# controller-ha-v5.net
KiCad netlist of a schematic drawn in EAGLE
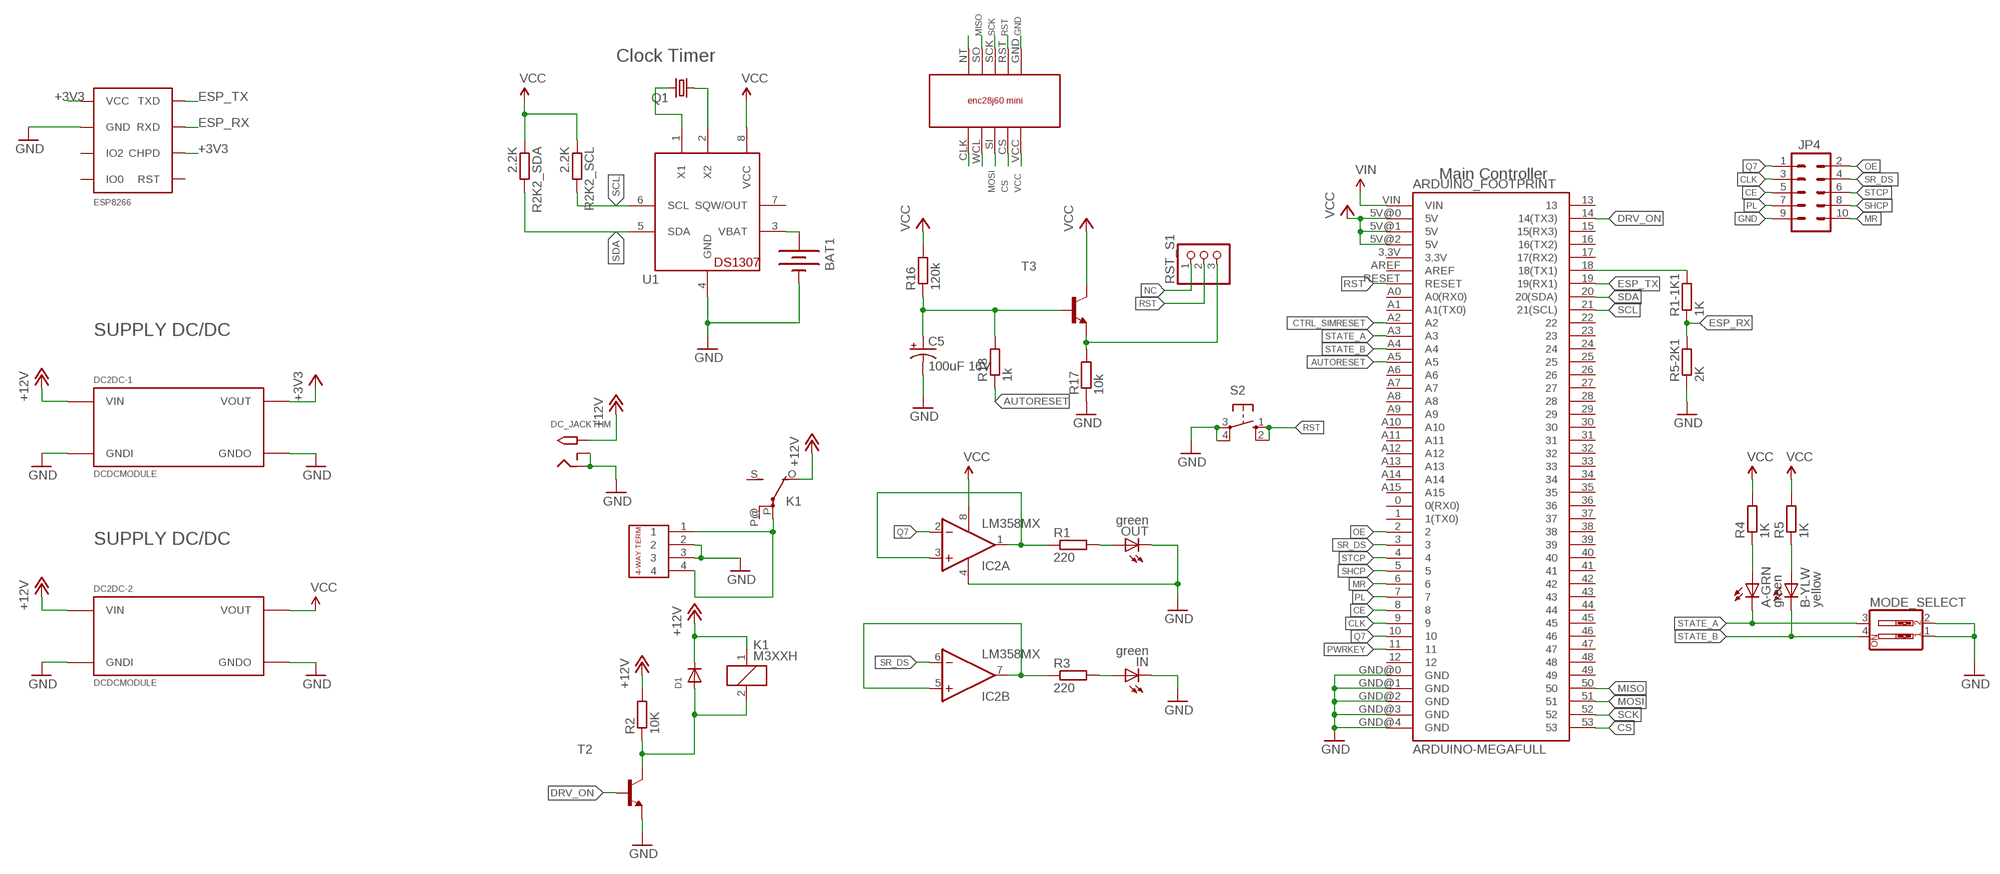
[diagram p0: schematic, sheet 1]

(export (version "E")
  (design (tool "Eeschema 10.0.6"))
  (components
    (comp (ref "4-WAY_L-TERMINAL")
      (value "4-PIN-CON-1759017")
      (footprint "eagle-import:4-PIN-CON-1759017")
      (libsource (lib "eagle-import") (part "4-PIN-CON-1759017"))
    )
    (comp (ref "A-GRN")
      (value "green")
      (footprint "eagle-import:CHIP-LED0805")
      (libsource (lib "eagle-import") (part "led_LEDCHIP-LED0805"))
    )
    (comp (ref "ARDUINO_FOOTPRINT")
      (value "ARDUINO-MEGAFULL")
      (footprint "eagle-import:ARDUINO_MEGA")
      (libsource (lib "eagle-import") (part "ARDUINO-MEGAFULL"))
    )
    (comp (ref "B-YLW")
      (value "yellow")
      (footprint "eagle-import:CHIP-LED0805")
      (libsource (lib "eagle-import") (part "led_LEDCHIP-LED0805"))
    )
    (comp (ref "BAT1")
      (value "BATTERY20PTH")
      (footprint "eagle-import:BATTCOM_20MM_PTH")
      (libsource (lib "eagle-import") (part "BATTERY20PTH"))
    )
    (comp (ref "C5")
      (value "100uF 16V")
      (footprint "eagle-import:153CLV-0605")
      (libsource (lib "eagle-import") (part "CPOL-US153CLV-0605"))
    )
    (comp (ref "D1")
      (value "DIODESMA")
      (footprint "eagle-import:SMADIODE")
      (libsource (lib "eagle-import") (part "DIODESMA"))
    )
    (comp (ref "DC2DC-1")
      (value "DCDCMODULE")
      (footprint "eagle-import:DCDCMODULE")
      (libsource (lib "eagle-import") (part "DCDCMODULE"))
    )
    (comp (ref "DC2DC-2")
      (value "DCDCMODULE")
      (footprint "eagle-import:DCDCMODULE")
      (libsource (lib "eagle-import") (part "DCDCMODULE"))
    )
    (comp (ref "DC_JACKTHM")
      (value "2.1MMJACKTHM")
      (footprint "eagle-import:PJ-102A")
      (libsource (lib "eagle-import") (part "2.1MMJACKTHM"))
    )
    (comp (ref "ESP8266")
      (value "ESP8266")
      (footprint "eagle-import:ESP8266")
      (libsource (lib "eagle-import") (part "ESP8266"))
    )
    (comp (ref "IC2")
      (value "LM358MX")
      (footprint "eagle-import:SO08")
      (libsource (lib "eagle-import") (part "LM358MX"))
    )
    (comp (ref "IN")
      (value "green")
      (footprint "eagle-import:CHIPLED_0805")
      (libsource (lib "eagle-import") (part "LEDCHIPLED_0805"))
    )
    (comp (ref "JP4")
      (value "M05X2RA")
      (footprint "eagle-import:2X5-RA")
      (libsource (lib "eagle-import") (part "M05X2RA"))
    )
    (comp (ref "K1")
      (value "M3XXH")
      (footprint "eagle-import:M3XXH")
      (libsource (lib "eagle-import") (part "M3XXH"))
    )
    (comp (ref "MODE_SELECT")
      (value "SW_DIP-2")
      (footprint "eagle-import:EDG-02")
      (libsource (lib "eagle-import") (part "SW_DIP-2"))
    )
    (comp (ref "OUT")
      (value "green")
      (footprint "eagle-import:CHIPLED_0805")
      (libsource (lib "eagle-import") (part "LEDCHIPLED_0805"))
    )
    (comp (ref "Q1")
      (value "CRYSTALTC26H")
      (footprint "eagle-import:TC26H")
      (libsource (lib "eagle-import") (part "CRYSTALTC26H"))
    )
    (comp (ref "R1")
      (value "220")
      (footprint "eagle-import:R0805")
      (libsource (lib "eagle-import") (part "resistor_R-EU_R0805"))
    )
    (comp (ref "R1-1K1")
      (value "1K")
      (footprint "eagle-import:R0603")
      (libsource (lib "eagle-import") (part "R-EU_R0603"))
    )
    (comp (ref "R2")
      (value "10K")
      (footprint "eagle-import:R0805")
      (libsource (lib "eagle-import") (part "resistor_R-EU_R0805"))
    )
    (comp (ref "R2K2_SCL")
      (value "2.2K")
      (footprint "eagle-import:R0603")
      (libsource (lib "eagle-import") (part "R-EU_R0603"))
    )
    (comp (ref "R2K2_SDA")
      (value "2.2K")
      (footprint "eagle-import:R0603")
      (libsource (lib "eagle-import") (part "R-EU_R0603"))
    )
    (comp (ref "R3")
      (value "220")
      (footprint "eagle-import:R0805")
      (libsource (lib "eagle-import") (part "resistor_R-EU_R0805"))
    )
    (comp (ref "R4")
      (value "1K")
      (footprint "eagle-import:R0805")
      (libsource (lib "eagle-import") (part "resistor_R-EU_R0805"))
    )
    (comp (ref "R5")
      (value "1K")
      (footprint "eagle-import:R0805")
      (libsource (lib "eagle-import") (part "resistor_R-EU_R0805"))
    )
    (comp (ref "R5-2K1")
      (value "2K")
      (footprint "eagle-import:R0603")
      (libsource (lib "eagle-import") (part "R-EU_R0603"))
    )
    (comp (ref "R16")
      (value "120k")
      (footprint "eagle-import:R0805")
      (libsource (lib "eagle-import") (part "R-EU_R0805"))
    )
    (comp (ref "R17")
      (value "10k")
      (footprint "eagle-import:R0805")
      (libsource (lib "eagle-import") (part "R-EU_R0805"))
    )
    (comp (ref "R18")
      (value "1k")
      (footprint "eagle-import:R0805")
      (libsource (lib "eagle-import") (part "R-EU_R0805"))
    )
    (comp (ref "RST_S1")
      (value "PINHD-1X3CB")
      (footprint "eagle-import:1X03-CLEANBIG")
      (libsource (lib "eagle-import") (part "PINHD-1X3CB"))
    )
    (comp (ref "S2")
      (value "10-XX")
      (footprint "eagle-import:B3F-10XX")
      (fields (field (name "MPN") "B3F-1000"))
      (libsource (lib "eagle-import") (part "10-XX"))
    )
    (comp (ref "T2")
      (value "MMBT2222ALT1-NPN-SOT23-BEC")
      (footprint "eagle-import:SOT23-BEC")
      (libsource (lib "eagle-import") (part "-NPN-SOT23-BECMMBT2222ALT1"))
    )
    (comp (ref "T3")
      (value "MMBT2222ALT1-NPN-SOT23-BEC")
      (footprint "eagle-import:SOT23-BEC")
      (libsource (lib "eagle-import") (part "-NPN-SOT23-BECMMBT2222ALT1"))
    )
    (comp (ref "U$2")
      (value "ENC28J60_MODULE_BOTTOM")
      (footprint "eagle-import:ENC28J60_MODULE_BOTTOM")
      (libsource (lib "eagle-import") (part "ENC28J60_MODULE_BOTTOM"))
    )
    (comp (ref "U1")
      (value "DS1307")
      (footprint "eagle-import:DIL08")
      (libsource (lib "eagle-import") (part "DS1307"))
    )
  )
  (nets
    (net (code "1") (name "+3V3") (class "Default")
      (node (ref "DC2DC-1") (pin "VOUT") (pinfunction "VOUT_VOUT") (pintype "bidirectional"))
      (node (ref "ESP8266") (pin "CHPD") (pinfunction "CHPD_CHPD") (pintype "bidirectional"))
      (node (ref "ESP8266") (pin "VCC") (pinfunction "VCC_VCC") (pintype "bidirectional"))
    )
    (net (code "2") (name "+12V") (class "Default")
      (node (ref "D1") (pin "C") (pinfunction "C_C") (pintype "passive"))
      (node (ref "DC2DC-1") (pin "VIN") (pinfunction "VIN_VIN") (pintype "bidirectional"))
      (node (ref "DC2DC-2") (pin "VIN") (pinfunction "VIN_VIN") (pintype "bidirectional"))
      (node (ref "DC_JACKTHM") (pin "TIP") (pinfunction "TIP_TIP") (pintype "bidirectional"))
      (node (ref "K1") (pin "1") (pinfunction "1_1") (pintype "passive"))
      (node (ref "K1") (pin "O") (pinfunction "O_O") (pintype "passive"))
      (node (ref "R2") (pin "2") (pinfunction "2_2") (pintype "passive"))
    )
    (net (code "3") (name "AUTORESET") (class "Default")
      (node (ref "ARDUINO_FOOTPRINT") (pin "A5") (pinfunction "A5_A5") (pintype "bidirectional"))
      (node (ref "R18") (pin "1") (pinfunction "1_1") (pintype "passive"))
    )
    (net (code "4") (name "CE") (class "Default")
      (node (ref "ARDUINO_FOOTPRINT") (pin "8") (pinfunction "8_8") (pintype "bidirectional"))
      (node (ref "JP4") (pin "5") (pinfunction "5_5") (pintype "passive"))
    )
    (net (code "5") (name "CLK") (class "Default")
      (node (ref "ARDUINO_FOOTPRINT") (pin "9") (pinfunction "9_9") (pintype "bidirectional"))
      (node (ref "JP4") (pin "3") (pinfunction "3_3") (pintype "passive"))
    )
    (net (code "6") (name "CS") (class "Default")
      (node (ref "ARDUINO_FOOTPRINT") (pin "53") (pinfunction "53_53") (pintype "bidirectional"))
      (node (ref "U$2") (pin "CS") (pinfunction "CS_CS") (pintype "bidirectional"))
    )
    (net (code "7") (name "CTRL_SIMRESET") (class "Default")
      (node (ref "ARDUINO_FOOTPRINT") (pin "A2") (pinfunction "A2_A2") (pintype "bidirectional"))
    )
    (net (code "8") (name "DRV_ON") (class "Default")
      (node (ref "ARDUINO_FOOTPRINT") (pin "14") (pinfunction "14(TX3)_14") (pintype "bidirectional"))
      (node (ref "T2") (pin "B") (pinfunction "B_B") (pintype "passive"))
    )
    (net (code "9") (name "ESP_RX") (class "Default")
      (node (ref "ESP8266") (pin "RXD") (pinfunction "RXD_RXD") (pintype "bidirectional"))
      (node (ref "R1-1K1") (pin "1") (pinfunction "1_1") (pintype "passive"))
      (node (ref "R5-2K1") (pin "2") (pinfunction "2_2") (pintype "passive"))
    )
    (net (code "10") (name "ESP_TX") (class "Default")
      (node (ref "ARDUINO_FOOTPRINT") (pin "19") (pinfunction "19(RX1)_19") (pintype "bidirectional"))
      (node (ref "ESP8266") (pin "TXD") (pinfunction "TXD_TXD") (pintype "bidirectional"))
    )
    (net (code "11") (name "GND") (class "Default")
      (node (ref "4-WAY_L-TERMINAL") (pin "2") (pinfunction "2_2") (pintype "bidirectional"))
      (node (ref "4-WAY_L-TERMINAL") (pin "3") (pinfunction "3_3") (pintype "bidirectional"))
      (node (ref "ARDUINO_FOOTPRINT") (pin "GND@0") (pinfunction "GND_GND@0") (pintype "bidirectional"))
      (node (ref "ARDUINO_FOOTPRINT") (pin "GND@1") (pinfunction "GND_GND@1") (pintype "bidirectional"))
      (node (ref "ARDUINO_FOOTPRINT") (pin "GND@2") (pinfunction "GND_GND@2") (pintype "bidirectional"))
      (node (ref "ARDUINO_FOOTPRINT") (pin "GND@3") (pinfunction "GND_GND@3") (pintype "bidirectional"))
      (node (ref "ARDUINO_FOOTPRINT") (pin "GND@4") (pinfunction "GND_GND@4") (pintype "bidirectional"))
      (node (ref "BAT1") (pin "2") (pinfunction "-_2") (pintype "power_in"))
      (node (ref "C5") (pin "-") (pinfunction "-_-") (pintype "passive"))
      (node (ref "DC2DC-1") (pin "GND#0") (pinfunction "GNDI_GND#0") (pintype "bidirectional"))
      (node (ref "DC2DC-1") (pin "GND#1") (pinfunction "GNDO_GND#1") (pintype "bidirectional"))
      (node (ref "DC2DC-2") (pin "GND#0") (pinfunction "GNDI_GND#0") (pintype "bidirectional"))
      (node (ref "DC2DC-2") (pin "GND#1") (pinfunction "GNDO_GND#1") (pintype "bidirectional"))
      (node (ref "DC_JACKTHM") (pin "RING") (pinfunction "RING_RING") (pintype "bidirectional"))
      (node (ref "DC_JACKTHM") (pin "RING_SW") (pinfunction "RING_SW_RING_SW") (pintype "bidirectional"))
      (node (ref "ESP8266") (pin "GND") (pinfunction "GND_GND") (pintype "bidirectional"))
      (node (ref "IC2") (pin "4") (pinfunction "V-_4") (pintype "power_in"))
      (node (ref "IN") (pin "C") (pinfunction "C_C") (pintype "passive"))
      (node (ref "JP4") (pin "9") (pinfunction "9_9") (pintype "passive"))
      (node (ref "MODE_SELECT") (pin "1") (pinfunction "1_1") (pintype "passive"))
      (node (ref "MODE_SELECT") (pin "2") (pinfunction "2_2") (pintype "passive"))
      (node (ref "OUT") (pin "C") (pinfunction "C_C") (pintype "passive"))
      (node (ref "R17") (pin "1") (pinfunction "1_1") (pintype "passive"))
      (node (ref "R5-2K1") (pin "1") (pinfunction "1_1") (pintype "passive"))
      (node (ref "S2") (pin "3") (pinfunction "P_3") (pintype "passive"))
      (node (ref "S2") (pin "4") (pinfunction "P1_4") (pintype "passive"))
      (node (ref "T2") (pin "E") (pinfunction "E_E") (pintype "passive"))
      (node (ref "U$2") (pin "GND") (pinfunction "GND_GND") (pintype "bidirectional"))
      (node (ref "U1") (pin "4") (pinfunction "GND_4") (pintype "power_in"))
    )
    (net (code "12") (name "MISO") (class "Default")
      (node (ref "ARDUINO_FOOTPRINT") (pin "50") (pinfunction "50_50") (pintype "bidirectional"))
      (node (ref "U$2") (pin "SO") (pinfunction "SO_SO") (pintype "bidirectional"))
    )
    (net (code "13") (name "MOSI") (class "Default")
      (node (ref "ARDUINO_FOOTPRINT") (pin "51") (pinfunction "51_51") (pintype "bidirectional"))
      (node (ref "U$2") (pin "SI") (pinfunction "SI_SI") (pintype "bidirectional"))
    )
    (net (code "14") (name "MR") (class "Default")
      (node (ref "ARDUINO_FOOTPRINT") (pin "6") (pinfunction "6_6") (pintype "bidirectional"))
      (node (ref "JP4") (pin "10") (pinfunction "10_10") (pintype "passive"))
    )
    (net (code "15") (name "NC") (class "Default")
      (node (ref "RST_S1") (pin "1") (pinfunction "1_1") (pintype "passive"))
    )
    (net (code "16") (name "Net-(4-WAY_L-TERMINAL-Pad1)") (class "Default")
      (node (ref "4-WAY_L-TERMINAL") (pin "1") (pinfunction "1_1") (pintype "bidirectional"))
      (node (ref "4-WAY_L-TERMINAL") (pin "4") (pinfunction "4_4") (pintype "bidirectional"))
      (node (ref "K1") (pin "P") (pinfunction "P_P") (pintype "passive"))
    )
    (net (code "17") (name "Net-(A-GRN-PadA)") (class "Default")
      (node (ref "A-GRN") (pin "A") (pinfunction "A_A") (pintype "passive"))
      (node (ref "R4") (pin "1") (pinfunction "1_1") (pintype "passive"))
    )
    (net (code "18") (name "Net-(ARDUINO_FOOTPRINT-18(TX1))") (class "Default")
      (node (ref "ARDUINO_FOOTPRINT") (pin "18") (pinfunction "18(TX1)_18") (pintype "bidirectional"))
      (node (ref "R1-1K1") (pin "2") (pinfunction "2_2") (pintype "passive"))
    )
    (net (code "19") (name "Net-(B-YLW-PadA)") (class "Default")
      (node (ref "B-YLW") (pin "A") (pinfunction "A_A") (pintype "passive"))
      (node (ref "R5") (pin "1") (pinfunction "1_1") (pintype "passive"))
    )
    (net (code "20") (name "Net-(BAT1-+)") (class "Default")
      (node (ref "BAT1") (pin "1") (pinfunction "+_1") (pintype "power_in"))
      (node (ref "U1") (pin "3") (pinfunction "VBAT_3") (pintype "power_in"))
    )
    (net (code "21") (name "Net-(C5-Pad+)") (class "Default")
      (node (ref "C5") (pin "+") (pinfunction "+_+") (pintype "passive"))
      (node (ref "R16") (pin "1") (pinfunction "1_1") (pintype "passive"))
      (node (ref "R18") (pin "2") (pinfunction "2_2") (pintype "passive"))
      (node (ref "T3") (pin "B") (pinfunction "B_B") (pintype "passive"))
    )
    (net (code "22") (name "Net-(D1-PadA)") (class "Default")
      (node (ref "D1") (pin "A") (pinfunction "A_A") (pintype "passive"))
      (node (ref "K1") (pin "2") (pinfunction "2_2") (pintype "passive"))
      (node (ref "R2") (pin "1") (pinfunction "1_1") (pintype "passive"))
      (node (ref "T2") (pin "C") (pinfunction "C_C") (pintype "passive"))
    )
    (net (code "23") (name "Net-(IC2A-+IN)") (class "Default")
      (node (ref "IC2") (pin "1") (pinfunction "OUT_1") (pintype "output"))
      (node (ref "IC2") (pin "3") (pinfunction "+IN_3") (pintype "input"))
      (node (ref "R1") (pin "1") (pinfunction "1_1") (pintype "passive"))
    )
    (net (code "24") (name "Net-(IC2B-+IN)") (class "Default")
      (node (ref "IC2") (pin "5") (pinfunction "+IN_5") (pintype "input"))
      (node (ref "IC2") (pin "7") (pinfunction "OUT_7") (pintype "output"))
      (node (ref "R3") (pin "1") (pinfunction "1_1") (pintype "passive"))
    )
    (net (code "25") (name "Net-(IN-PadA)") (class "Default")
      (node (ref "IN") (pin "A") (pinfunction "A_A") (pintype "passive"))
      (node (ref "R3") (pin "2") (pinfunction "2_2") (pintype "passive"))
    )
    (net (code "26") (name "Net-(OUT-PadA)") (class "Default")
      (node (ref "OUT") (pin "A") (pinfunction "A_A") (pintype "passive"))
      (node (ref "R1") (pin "2") (pinfunction "2_2") (pintype "passive"))
    )
    (net (code "27") (name "Net-(R17-Pad2)") (class "Default")
      (node (ref "R17") (pin "2") (pinfunction "2_2") (pintype "passive"))
      (node (ref "RST_S1") (pin "3") (pinfunction "3_3") (pintype "passive"))
      (node (ref "T3") (pin "E") (pinfunction "E_E") (pintype "passive"))
    )
    (net (code "28") (name "Net-(U1-X1)") (class "Default")
      (node (ref "Q1") (pin "2") (pinfunction "2_2") (pintype "passive"))
      (node (ref "U1") (pin "1") (pinfunction "X1_1") (pintype "passive"))
    )
    (net (code "29") (name "Net-(U1-X2)") (class "Default")
      (node (ref "Q1") (pin "1") (pinfunction "1_1") (pintype "passive"))
      (node (ref "U1") (pin "2") (pinfunction "X2_2") (pintype "passive"))
    )
    (net (code "30") (name "OE") (class "Default")
      (node (ref "ARDUINO_FOOTPRINT") (pin "2") (pinfunction "2_2") (pintype "bidirectional"))
      (node (ref "JP4") (pin "2") (pinfunction "2_2") (pintype "passive"))
    )
    (net (code "31") (name "PL") (class "Default")
      (node (ref "ARDUINO_FOOTPRINT") (pin "7") (pinfunction "7_7") (pintype "bidirectional"))
      (node (ref "JP4") (pin "7") (pinfunction "7_7") (pintype "passive"))
    )
    (net (code "32") (name "PWRKEY") (class "Default")
      (node (ref "ARDUINO_FOOTPRINT") (pin "11") (pinfunction "11_11") (pintype "bidirectional"))
    )
    (net (code "33") (name "Q7") (class "Default")
      (node (ref "ARDUINO_FOOTPRINT") (pin "10") (pinfunction "10_10") (pintype "bidirectional"))
      (node (ref "IC2") (pin "2") (pinfunction "-IN_2") (pintype "input"))
      (node (ref "JP4") (pin "1") (pinfunction "1_1") (pintype "passive"))
    )
    (net (code "34") (name "RST") (class "Default")
      (node (ref "ARDUINO_FOOTPRINT") (pin "RESET") (pinfunction "RESET_RESET") (pintype "bidirectional"))
      (node (ref "RST_S1") (pin "2") (pinfunction "2_2") (pintype "passive"))
      (node (ref "S2") (pin "1") (pinfunction "S_1") (pintype "passive"))
      (node (ref "S2") (pin "2") (pinfunction "S1_2") (pintype "passive"))
      (node (ref "U$2") (pin "RST") (pinfunction "RST_RST") (pintype "bidirectional"))
    )
    (net (code "35") (name "SCK") (class "Default")
      (node (ref "ARDUINO_FOOTPRINT") (pin "52") (pinfunction "52_52") (pintype "bidirectional"))
      (node (ref "U$2") (pin "SCK") (pinfunction "SCK_SCK") (pintype "bidirectional"))
    )
    (net (code "36") (name "SCL") (class "Default")
      (node (ref "ARDUINO_FOOTPRINT") (pin "21") (pinfunction "21(SCL)_21") (pintype "bidirectional"))
      (node (ref "R2K2_SCL") (pin "2") (pinfunction "2_2") (pintype "passive"))
      (node (ref "U1") (pin "6") (pinfunction "SCL_6") (pintype "bidirectional"))
    )
    (net (code "37") (name "SDA") (class "Default")
      (node (ref "ARDUINO_FOOTPRINT") (pin "20") (pinfunction "20(SDA)_20") (pintype "bidirectional"))
      (node (ref "R2K2_SDA") (pin "2") (pinfunction "2_2") (pintype "passive"))
      (node (ref "U1") (pin "5") (pinfunction "SDA_5") (pintype "bidirectional"))
    )
    (net (code "38") (name "SHCP") (class "Default")
      (node (ref "ARDUINO_FOOTPRINT") (pin "5") (pinfunction "5_5") (pintype "bidirectional"))
      (node (ref "JP4") (pin "8") (pinfunction "8_8") (pintype "passive"))
    )
    (net (code "39") (name "SR_DS") (class "Default")
      (node (ref "ARDUINO_FOOTPRINT") (pin "3") (pinfunction "3_3") (pintype "bidirectional"))
      (node (ref "IC2") (pin "6") (pinfunction "-IN_6") (pintype "input"))
      (node (ref "JP4") (pin "4") (pinfunction "4_4") (pintype "passive"))
    )
    (net (code "40") (name "STATE_A") (class "Default")
      (node (ref "A-GRN") (pin "C") (pinfunction "C_C") (pintype "passive"))
      (node (ref "ARDUINO_FOOTPRINT") (pin "A3") (pinfunction "A3_A3") (pintype "bidirectional"))
      (node (ref "MODE_SELECT") (pin "3") (pinfunction "3_3") (pintype "passive"))
    )
    (net (code "41") (name "STATE_B") (class "Default")
      (node (ref "ARDUINO_FOOTPRINT") (pin "A4") (pinfunction "A4_A4") (pintype "bidirectional"))
      (node (ref "B-YLW") (pin "C") (pinfunction "C_C") (pintype "passive"))
      (node (ref "MODE_SELECT") (pin "4") (pinfunction "4_4") (pintype "passive"))
    )
    (net (code "42") (name "STCP") (class "Default")
      (node (ref "ARDUINO_FOOTPRINT") (pin "4") (pinfunction "4_4") (pintype "bidirectional"))
      (node (ref "JP4") (pin "6") (pinfunction "6_6") (pintype "passive"))
    )
    (net (code "43") (name "VCC") (class "Default")
      (node (ref "ARDUINO_FOOTPRINT") (pin "5V@0") (pinfunction "5V_5V@0") (pintype "bidirectional"))
      (node (ref "ARDUINO_FOOTPRINT") (pin "5V@1") (pinfunction "5V_5V@1") (pintype "bidirectional"))
      (node (ref "ARDUINO_FOOTPRINT") (pin "5V@2") (pinfunction "5V_5V@2") (pintype "bidirectional"))
      (node (ref "DC2DC-2") (pin "VOUT") (pinfunction "VOUT_VOUT") (pintype "bidirectional"))
      (node (ref "IC2") (pin "8") (pinfunction "V+_8") (pintype "power_in"))
      (node (ref "R16") (pin "2") (pinfunction "2_2") (pintype "passive"))
      (node (ref "R2K2_SCL") (pin "1") (pinfunction "1_1") (pintype "passive"))
      (node (ref "R2K2_SDA") (pin "1") (pinfunction "1_1") (pintype "passive"))
      (node (ref "R4") (pin "2") (pinfunction "2_2") (pintype "passive"))
      (node (ref "R5") (pin "2") (pinfunction "2_2") (pintype "passive"))
      (node (ref "T3") (pin "C") (pinfunction "C_C") (pintype "passive"))
      (node (ref "U$2") (pin "VCC") (pinfunction "VCC_VCC") (pintype "bidirectional"))
      (node (ref "U1") (pin "8") (pinfunction "VCC_8") (pintype "power_in"))
    )
    (net (code "44") (name "VIN") (class "Default")
      (node (ref "ARDUINO_FOOTPRINT") (pin "VIN") (pinfunction "VIN_VIN") (pintype "bidirectional"))
    )
    (net (code "45") (name "unconnected-(ARDUINO_FOOTPRINT-0(RX0)-Pad0)") (class "Default")
      (node (ref "ARDUINO_FOOTPRINT") (pin "0") (pinfunction "0(RX0)_0") (pintype "bidirectional"))
    )
    (net (code "46") (name "unconnected-(ARDUINO_FOOTPRINT-1(TX0)-Pad1)") (class "Default")
      (node (ref "ARDUINO_FOOTPRINT") (pin "1") (pinfunction "1(TX0)_1") (pintype "bidirectional"))
    )
    (net (code "47") (name "unconnected-(ARDUINO_FOOTPRINT-15(RX3)-Pad15)") (class "Default")
      (node (ref "ARDUINO_FOOTPRINT") (pin "15") (pinfunction "15(RX3)_15") (pintype "bidirectional"))
    )
    (net (code "48") (name "unconnected-(ARDUINO_FOOTPRINT-16(TX2)-Pad16)") (class "Default")
      (node (ref "ARDUINO_FOOTPRINT") (pin "16") (pinfunction "16(TX2)_16") (pintype "bidirectional"))
    )
    (net (code "49") (name "unconnected-(ARDUINO_FOOTPRINT-17(RX2)-Pad17)") (class "Default")
      (node (ref "ARDUINO_FOOTPRINT") (pin "17") (pinfunction "17(RX2)_17") (pintype "bidirectional"))
    )
    (net (code "50") (name "unconnected-(ARDUINO_FOOTPRINT-A0(RX0)-PadA0)") (class "Default")
      (node (ref "ARDUINO_FOOTPRINT") (pin "A0") (pinfunction "A0(RX0)_A0") (pintype "bidirectional"))
    )
    (net (code "51") (name "unconnected-(ARDUINO_FOOTPRINT-A1(TX0)-PadA1)") (class "Default")
      (node (ref "ARDUINO_FOOTPRINT") (pin "A1") (pinfunction "A1(TX0)_A1") (pintype "bidirectional"))
    )
    (net (code "52") (name "unconnected-(ARDUINO_FOOTPRINT-Pad3.3V)") (class "Default")
      (node (ref "ARDUINO_FOOTPRINT") (pin "3.3V") (pinfunction "3.3V_3.3V") (pintype "bidirectional"))
    )
    (net (code "53") (name "unconnected-(ARDUINO_FOOTPRINT-Pad12)") (class "Default")
      (node (ref "ARDUINO_FOOTPRINT") (pin "12") (pinfunction "12_12") (pintype "bidirectional"))
    )
    (net (code "54") (name "unconnected-(ARDUINO_FOOTPRINT-Pad13)") (class "Default")
      (node (ref "ARDUINO_FOOTPRINT") (pin "13") (pinfunction "13_13") (pintype "bidirectional"))
    )
    (net (code "55") (name "unconnected-(ARDUINO_FOOTPRINT-Pad22)") (class "Default")
      (node (ref "ARDUINO_FOOTPRINT") (pin "22") (pinfunction "22_22") (pintype "bidirectional"))
    )
    (net (code "56") (name "unconnected-(ARDUINO_FOOTPRINT-Pad23)") (class "Default")
      (node (ref "ARDUINO_FOOTPRINT") (pin "23") (pinfunction "23_23") (pintype "bidirectional"))
    )
    (net (code "57") (name "unconnected-(ARDUINO_FOOTPRINT-Pad24)") (class "Default")
      (node (ref "ARDUINO_FOOTPRINT") (pin "24") (pinfunction "24_24") (pintype "bidirectional"))
    )
    (net (code "58") (name "unconnected-(ARDUINO_FOOTPRINT-Pad25)") (class "Default")
      (node (ref "ARDUINO_FOOTPRINT") (pin "25") (pinfunction "25_25") (pintype "bidirectional"))
    )
    (net (code "59") (name "unconnected-(ARDUINO_FOOTPRINT-Pad26)") (class "Default")
      (node (ref "ARDUINO_FOOTPRINT") (pin "26") (pinfunction "26_26") (pintype "bidirectional"))
    )
    (net (code "60") (name "unconnected-(ARDUINO_FOOTPRINT-Pad27)") (class "Default")
      (node (ref "ARDUINO_FOOTPRINT") (pin "27") (pinfunction "27_27") (pintype "bidirectional"))
    )
    (net (code "61") (name "unconnected-(ARDUINO_FOOTPRINT-Pad28)") (class "Default")
      (node (ref "ARDUINO_FOOTPRINT") (pin "28") (pinfunction "28_28") (pintype "bidirectional"))
    )
    (net (code "62") (name "unconnected-(ARDUINO_FOOTPRINT-Pad29)") (class "Default")
      (node (ref "ARDUINO_FOOTPRINT") (pin "29") (pinfunction "29_29") (pintype "bidirectional"))
    )
    (net (code "63") (name "unconnected-(ARDUINO_FOOTPRINT-Pad30)") (class "Default")
      (node (ref "ARDUINO_FOOTPRINT") (pin "30") (pinfunction "30_30") (pintype "bidirectional"))
    )
    (net (code "64") (name "unconnected-(ARDUINO_FOOTPRINT-Pad31)") (class "Default")
      (node (ref "ARDUINO_FOOTPRINT") (pin "31") (pinfunction "31_31") (pintype "bidirectional"))
    )
    (net (code "65") (name "unconnected-(ARDUINO_FOOTPRINT-Pad32)") (class "Default")
      (node (ref "ARDUINO_FOOTPRINT") (pin "32") (pinfunction "32_32") (pintype "bidirectional"))
    )
    (net (code "66") (name "unconnected-(ARDUINO_FOOTPRINT-Pad33)") (class "Default")
      (node (ref "ARDUINO_FOOTPRINT") (pin "33") (pinfunction "33_33") (pintype "bidirectional"))
    )
    (net (code "67") (name "unconnected-(ARDUINO_FOOTPRINT-Pad34)") (class "Default")
      (node (ref "ARDUINO_FOOTPRINT") (pin "34") (pinfunction "34_34") (pintype "bidirectional"))
    )
    (net (code "68") (name "unconnected-(ARDUINO_FOOTPRINT-Pad35)") (class "Default")
      (node (ref "ARDUINO_FOOTPRINT") (pin "35") (pinfunction "35_35") (pintype "bidirectional"))
    )
    (net (code "69") (name "unconnected-(ARDUINO_FOOTPRINT-Pad36)") (class "Default")
      (node (ref "ARDUINO_FOOTPRINT") (pin "36") (pinfunction "36_36") (pintype "bidirectional"))
    )
    (net (code "70") (name "unconnected-(ARDUINO_FOOTPRINT-Pad37)") (class "Default")
      (node (ref "ARDUINO_FOOTPRINT") (pin "37") (pinfunction "37_37") (pintype "bidirectional"))
    )
    (net (code "71") (name "unconnected-(ARDUINO_FOOTPRINT-Pad38)") (class "Default")
      (node (ref "ARDUINO_FOOTPRINT") (pin "38") (pinfunction "38_38") (pintype "bidirectional"))
    )
    (net (code "72") (name "unconnected-(ARDUINO_FOOTPRINT-Pad39)") (class "Default")
      (node (ref "ARDUINO_FOOTPRINT") (pin "39") (pinfunction "39_39") (pintype "bidirectional"))
    )
    (net (code "73") (name "unconnected-(ARDUINO_FOOTPRINT-Pad40)") (class "Default")
      (node (ref "ARDUINO_FOOTPRINT") (pin "40") (pinfunction "40_40") (pintype "bidirectional"))
    )
    (net (code "74") (name "unconnected-(ARDUINO_FOOTPRINT-Pad41)") (class "Default")
      (node (ref "ARDUINO_FOOTPRINT") (pin "41") (pinfunction "41_41") (pintype "bidirectional"))
    )
    (net (code "75") (name "unconnected-(ARDUINO_FOOTPRINT-Pad42)") (class "Default")
      (node (ref "ARDUINO_FOOTPRINT") (pin "42") (pinfunction "42_42") (pintype "bidirectional"))
    )
    (net (code "76") (name "unconnected-(ARDUINO_FOOTPRINT-Pad43)") (class "Default")
      (node (ref "ARDUINO_FOOTPRINT") (pin "43") (pinfunction "43_43") (pintype "bidirectional"))
    )
    (net (code "77") (name "unconnected-(ARDUINO_FOOTPRINT-Pad44)") (class "Default")
      (node (ref "ARDUINO_FOOTPRINT") (pin "44") (pinfunction "44_44") (pintype "bidirectional"))
    )
    (net (code "78") (name "unconnected-(ARDUINO_FOOTPRINT-Pad45)") (class "Default")
      (node (ref "ARDUINO_FOOTPRINT") (pin "45") (pinfunction "45_45") (pintype "bidirectional"))
    )
    (net (code "79") (name "unconnected-(ARDUINO_FOOTPRINT-Pad46)") (class "Default")
      (node (ref "ARDUINO_FOOTPRINT") (pin "46") (pinfunction "46_46") (pintype "bidirectional"))
    )
    (net (code "80") (name "unconnected-(ARDUINO_FOOTPRINT-Pad47)") (class "Default")
      (node (ref "ARDUINO_FOOTPRINT") (pin "47") (pinfunction "47_47") (pintype "bidirectional"))
    )
    (net (code "81") (name "unconnected-(ARDUINO_FOOTPRINT-Pad48)") (class "Default")
      (node (ref "ARDUINO_FOOTPRINT") (pin "48") (pinfunction "48_48") (pintype "bidirectional"))
    )
    (net (code "82") (name "unconnected-(ARDUINO_FOOTPRINT-Pad49)") (class "Default")
      (node (ref "ARDUINO_FOOTPRINT") (pin "49") (pinfunction "49_49") (pintype "bidirectional"))
    )
    (net (code "83") (name "unconnected-(ARDUINO_FOOTPRINT-PadA6)") (class "Default")
      (node (ref "ARDUINO_FOOTPRINT") (pin "A6") (pinfunction "A6_A6") (pintype "bidirectional"))
    )
    (net (code "84") (name "unconnected-(ARDUINO_FOOTPRINT-PadA7)") (class "Default")
      (node (ref "ARDUINO_FOOTPRINT") (pin "A7") (pinfunction "A7_A7") (pintype "bidirectional"))
    )
    (net (code "85") (name "unconnected-(ARDUINO_FOOTPRINT-PadA8)") (class "Default")
      (node (ref "ARDUINO_FOOTPRINT") (pin "A8") (pinfunction "A8_A8") (pintype "bidirectional"))
    )
    (net (code "86") (name "unconnected-(ARDUINO_FOOTPRINT-PadA9)") (class "Default")
      (node (ref "ARDUINO_FOOTPRINT") (pin "A9") (pinfunction "A9_A9") (pintype "bidirectional"))
    )
    (net (code "87") (name "unconnected-(ARDUINO_FOOTPRINT-PadA10)") (class "Default")
      (node (ref "ARDUINO_FOOTPRINT") (pin "A10") (pinfunction "A10_A10") (pintype "bidirectional"))
    )
    (net (code "88") (name "unconnected-(ARDUINO_FOOTPRINT-PadA11)") (class "Default")
      (node (ref "ARDUINO_FOOTPRINT") (pin "A11") (pinfunction "A11_A11") (pintype "bidirectional"))
    )
    (net (code "89") (name "unconnected-(ARDUINO_FOOTPRINT-PadA12)") (class "Default")
      (node (ref "ARDUINO_FOOTPRINT") (pin "A12") (pinfunction "A12_A12") (pintype "bidirectional"))
    )
    (net (code "90") (name "unconnected-(ARDUINO_FOOTPRINT-PadA13)") (class "Default")
      (node (ref "ARDUINO_FOOTPRINT") (pin "A13") (pinfunction "A13_A13") (pintype "bidirectional"))
    )
    (net (code "91") (name "unconnected-(ARDUINO_FOOTPRINT-PadA14)") (class "Default")
      (node (ref "ARDUINO_FOOTPRINT") (pin "A14") (pinfunction "A14_A14") (pintype "bidirectional"))
    )
    (net (code "92") (name "unconnected-(ARDUINO_FOOTPRINT-PadA15)") (class "Default")
      (node (ref "ARDUINO_FOOTPRINT") (pin "A15") (pinfunction "A15_A15") (pintype "bidirectional"))
    )
    (net (code "93") (name "unconnected-(ARDUINO_FOOTPRINT-PadAREF)") (class "Default")
      (node (ref "ARDUINO_FOOTPRINT") (pin "AREF") (pinfunction "AREF_AREF") (pintype "bidirectional"))
    )
    (net (code "94") (name "unconnected-(ESP8266-PadIO0)") (class "Default")
      (node (ref "ESP8266") (pin "IO0") (pinfunction "IO0_IO0") (pintype "bidirectional"))
    )
    (net (code "95") (name "unconnected-(ESP8266-PadIO2)") (class "Default")
      (node (ref "ESP8266") (pin "IO2") (pinfunction "IO2_IO2") (pintype "bidirectional"))
    )
    (net (code "96") (name "unconnected-(ESP8266-PadRST)") (class "Default")
      (node (ref "ESP8266") (pin "RST") (pinfunction "RST_RST") (pintype "bidirectional"))
    )
    (net (code "97") (name "unconnected-(K1-PadS)") (class "Default")
      (node (ref "K1") (pin "S") (pinfunction "S_S") (pintype "passive"))
    )
    (net (code "98") (name "unconnected-(K1B-P-PadP@)") (class "Default")
      (node (ref "K1") (pin "P@") (pinfunction "P_P@") (pintype "passive"))
    )
    (net (code "99") (name "unconnected-(U$2-PadCLK)") (class "Default")
      (node (ref "U$2") (pin "CLK") (pinfunction "CLK_CLK") (pintype "bidirectional"))
    )
    (net (code "100") (name "unconnected-(U$2-PadNT)") (class "Default")
      (node (ref "U$2") (pin "NT") (pinfunction "NT_NT") (pintype "bidirectional"))
    )
    (net (code "101") (name "unconnected-(U$2-PadWCL)") (class "Default")
      (node (ref "U$2") (pin "WCL") (pinfunction "WCL_WCL") (pintype "bidirectional"))
    )
    (net (code "102") (name "unconnected-(U1-SQW{slash}OUT-Pad7)") (class "Default")
      (node (ref "U1") (pin "7") (pinfunction "SQW/OUT_7") (pintype "bidirectional"))
    )
  )
)
